# InkTime_v6.net
KiCad netlist of a schematic drawn in EAGLE
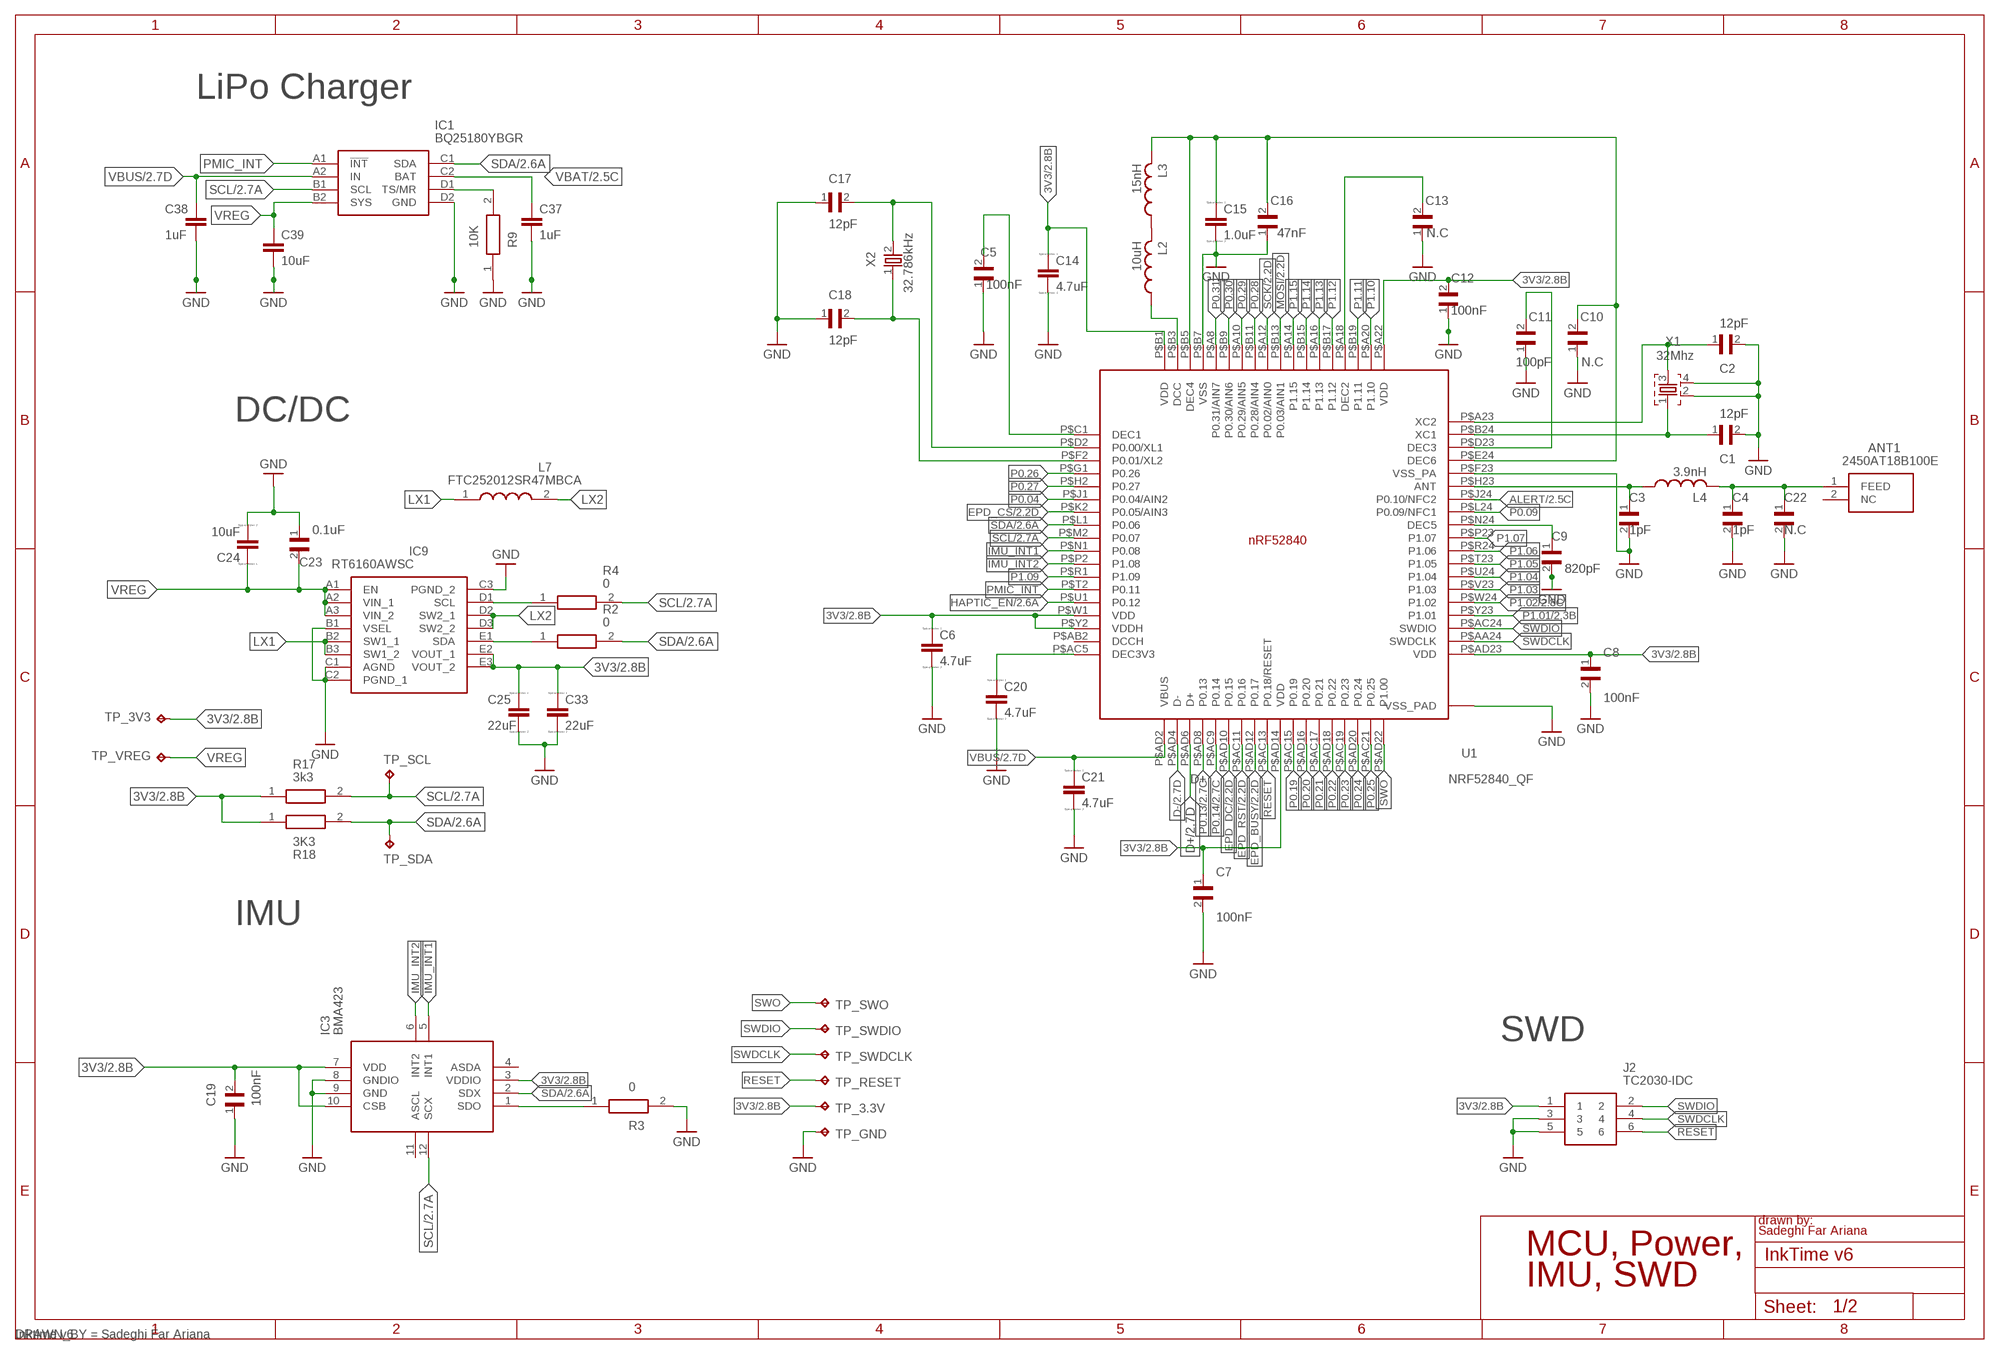
[diagram p0: schematic, sheet 1]
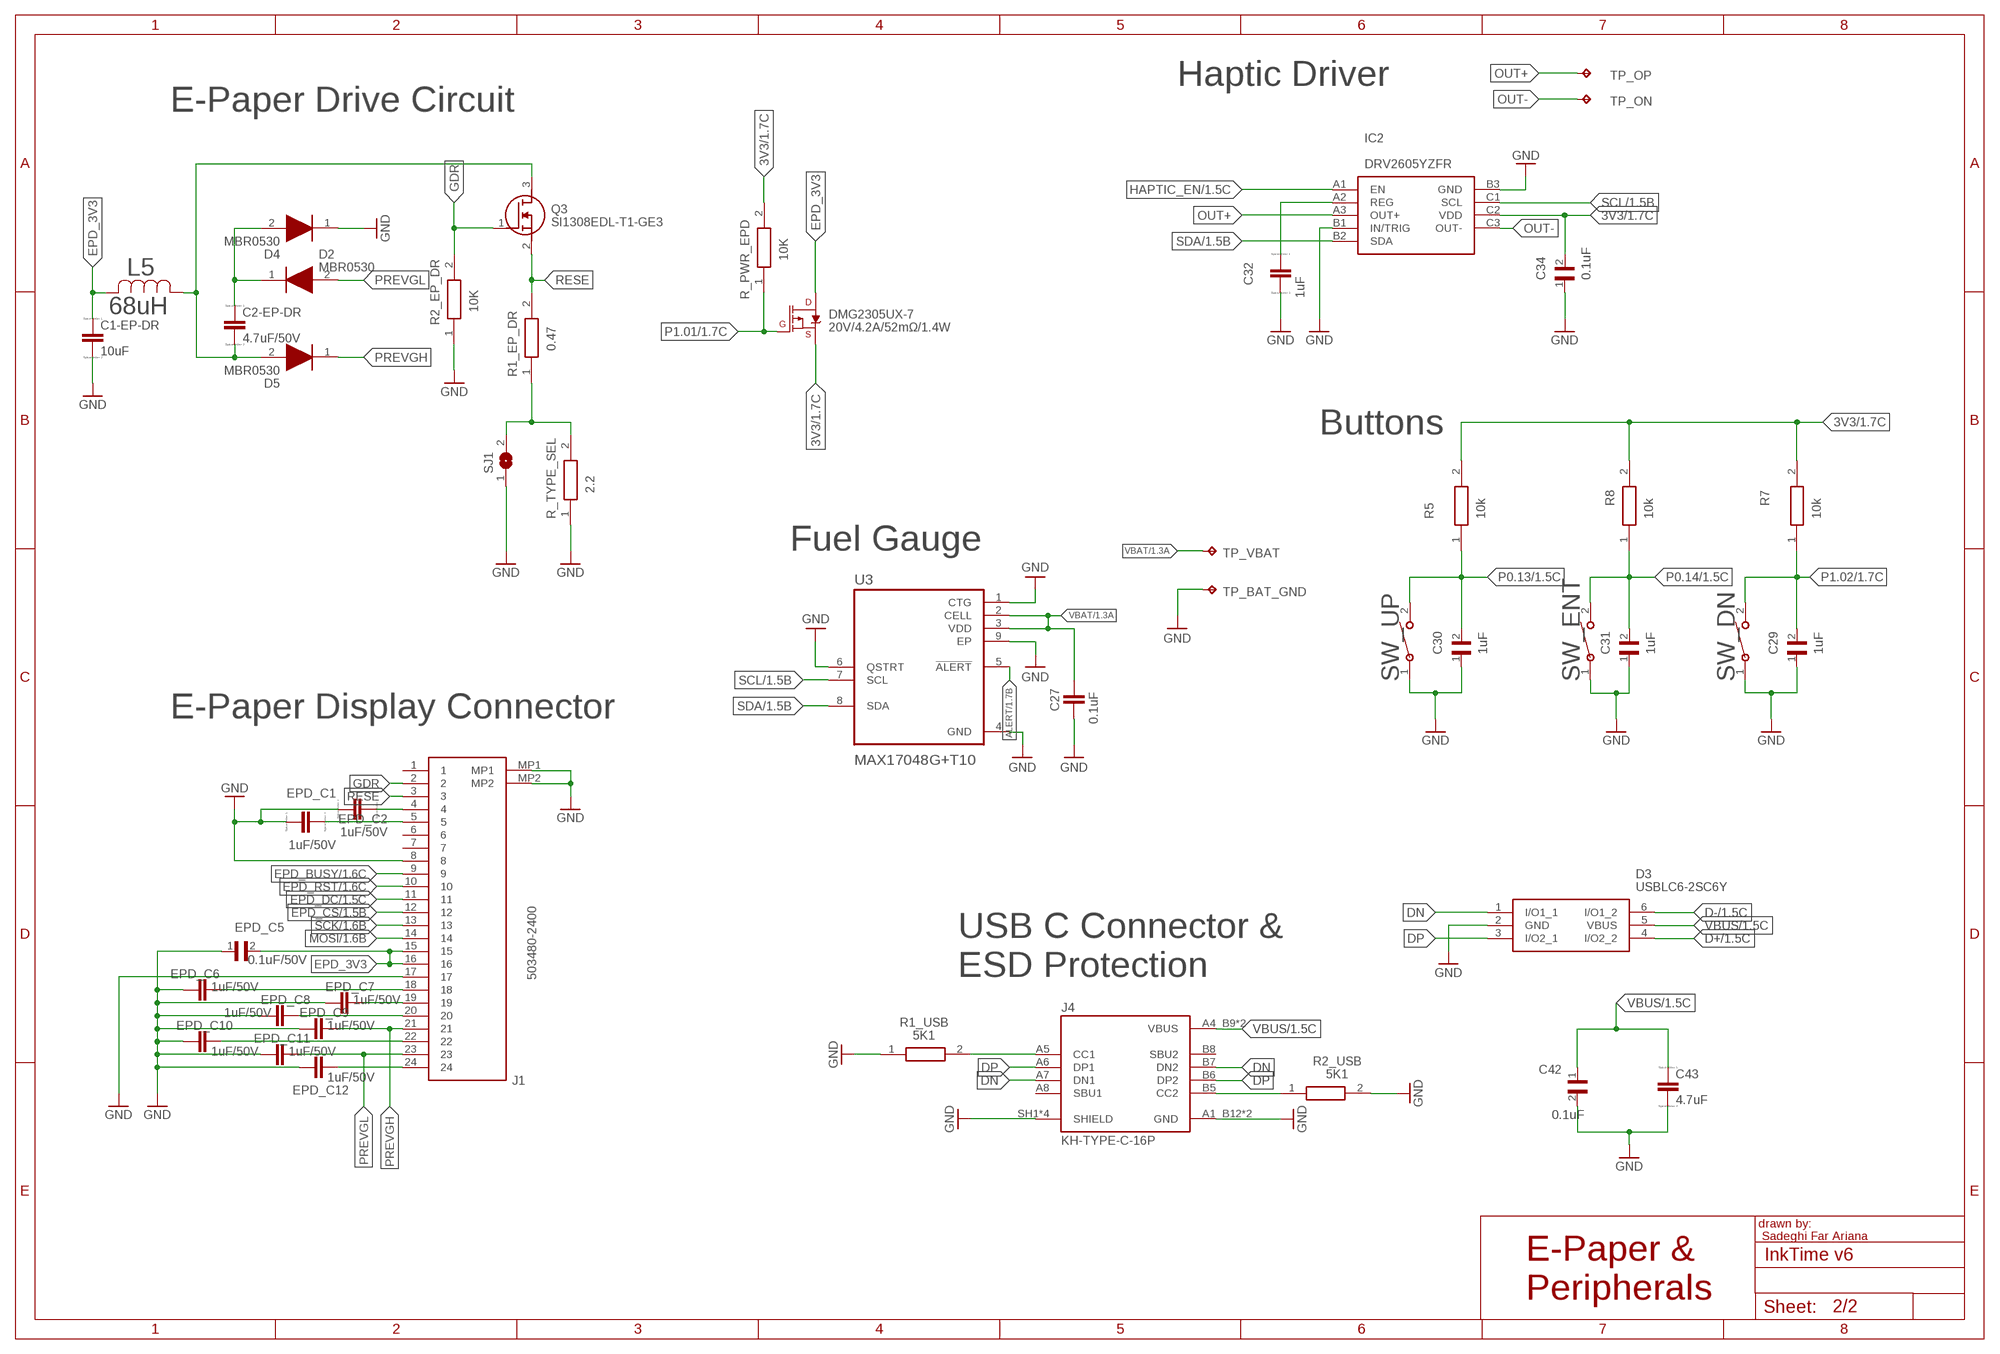
[diagram p1: schematic, sheet 2]

(export (version "E")
  (design (tool "Eeschema 10.0.6"))
  (components
    (comp (ref "C1-EP-DR")
      (value "10uF")
      (footprint "eagle-import:ESP32_C6_LIBRARY_1_ESP32_WROVER_EAGLE-LTSPICE_C0402")
      (libsource (lib "eagle-import") (part "ESP32_C6_LIBRARY_1_ESP32_WROVER_EAGLE-LTSPICE_CC0402"))
    )
    (comp (ref "C2-EP-DR")
      (value "4.7uF/50V")
      (footprint "eagle-import:ESP32_C6_LIBRARY_1_ESP32_WROVER_EAGLE-LTSPICE_C0402")
      (libsource (lib "eagle-import") (part "ESP32_C6_LIBRARY_1_ESP32_WROVER_EAGLE-LTSPICE_CC0402"))
    )
    (comp (ref "C27")
      (value "0.1uF")
      (footprint "eagle-import:NORDIC_NRF_3_RESC0201_L")
      (libsource (lib "eagle-import") (part "NORDIC_NRF_3_CAPACITOR_0201_L"))
    )
    (comp (ref "C29")
      (value "1uF")
      (footprint "eagle-import:GRM011R60J152KE01L_2_CAPC0201X13N")
      (fields (field (name "MF") "Murata") (field (name "MP") "GRM011R60J152KE01L"))
      (libsource (lib "eagle-import") (part "GRM011R60J152KE01L_2_GRM011R60J152KE01L"))
    )
    (comp (ref "C30")
      (value "1uF")
      (footprint "eagle-import:GRM011R60J152KE01L_2_CAPC0201X13N")
      (fields (field (name "MF") "Murata") (field (name "MP") "GRM011R60J152KE01L"))
      (libsource (lib "eagle-import") (part "GRM011R60J152KE01L_2_GRM011R60J152KE01L"))
    )
    (comp (ref "C31")
      (value "1uF")
      (footprint "eagle-import:GRM011R60J152KE01L_2_CAPC0201X13N")
      (fields (field (name "MF") "Murata") (field (name "MP") "GRM011R60J152KE01L"))
      (libsource (lib "eagle-import") (part "GRM011R60J152KE01L_2_GRM011R60J152KE01L"))
    )
    (comp (ref "C32")
      (value "1uF")
      (footprint "eagle-import:ESP32_C6_LIBRARY_1_ESP32_WROVER_EAGLE-LTSPICE_C0402")
      (libsource (lib "eagle-import") (part "ESP32_C6_LIBRARY_1_ESP32_WROVER_EAGLE-LTSPICE_CC0402"))
    )
    (comp (ref "C34")
      (value "0.1uF")
      (footprint "eagle-import:GRM011R60J152KE01L_2_CAPC0201X13N")
      (fields (field (name "MF") "Murata") (field (name "MP") "GRM011R60J152KE01L"))
      (libsource (lib "eagle-import") (part "GRM011R60J152KE01L_2_GRM011R60J152KE01L"))
    )
    (comp (ref "C42")
      (value "0.1uF")
      (footprint "eagle-import:GRM011R60J152KE01L_2_CAPC0201X13N")
      (fields (field (name "MF") "Murata") (field (name "MP") "GRM011R60J152KE01L"))
      (libsource (lib "eagle-import") (part "GRM011R60J152KE01L_2_GRM011R60J152KE01L"))
    )
    (comp (ref "C43")
      (value "4.7uF")
      (footprint "eagle-import:ESP32_C6_LIBRARY_1_ESP32_WROVER_EAGLE-LTSPICE_C0402")
      (libsource (lib "eagle-import") (part "ESP32_C6_LIBRARY_1_ESP32_WROVER_EAGLE-LTSPICE_CC0402"))
    )
    (comp (ref "D2")
      (value "MBR0530")
      (footprint "eagle-import:ESP32_C6_LIBRARY_5_SOD3716X135N")
      (fields (field (name "MF") "ON Semiconductor"))
      (libsource (lib "eagle-import") (part "ESP32_C6_LIBRARY_5_MBR0530"))
    )
    (comp (ref "D3")
      (value "USBLC6-2SC6Y")
      (footprint "eagle-import:ESP32_C6_LIBRARY_3_SOT95P280X145-6N")
      (fields (field (name "MF") "STMicroelectronics"))
      (libsource (lib "eagle-import") (part "ESP32_C6_LIBRARY_3_USBLC6-2SC6Y"))
    )
    (comp (ref "D4")
      (value "MBR0530")
      (footprint "eagle-import:ESP32_C6_LIBRARY_5_SOD3716X135N")
      (fields (field (name "MF") "ON Semiconductor"))
      (libsource (lib "eagle-import") (part "ESP32_C6_LIBRARY_5_MBR0530"))
    )
    (comp (ref "D5")
      (value "MBR0530")
      (footprint "eagle-import:ESP32_C6_LIBRARY_5_SOD3716X135N")
      (fields (field (name "MF") "ON Semiconductor"))
      (libsource (lib "eagle-import") (part "ESP32_C6_LIBRARY_5_MBR0530"))
    )
    (comp (ref "DMG2305UX-7")
      (value "20V/4.2A/52mΩ/1.4W")
      (footprint "eagle-import:ESP32_C6_LIBRARY_4_ESP32_C6_LIBRARY_4_ESP32_C6_LIBRARY_4_ESP32_C6_LIBRARY_4_ESP32_WROVER_SPARKFUN-DISCRETESEMI_SOT23-3")
      (libsource (lib "eagle-import") (part "ESP32_C6_LIBRARY_4_ESP32_WROVER_SPARKFUN-DISCRETESEMI_MOSFET_PCH-DMG2305UX-7"))
    )
    (comp (ref "EPD_C1")
      (value "1uF/50V")
      (footprint "eagle-import:ESP32_C6_LIBRARY_1_ESP32_WROVER_EAGLE-LTSPICE_C0402")
      (libsource (lib "eagle-import") (part "ESP32_C6_LIBRARY_1_ESP32_WROVER_EAGLE-LTSPICE_CC0402"))
    )
    (comp (ref "EPD_C2")
      (value "1uF/50V")
      (footprint "eagle-import:ESP32_C6_LIBRARY_1_ESP32_WROVER_EAGLE-LTSPICE_C0402")
      (libsource (lib "eagle-import") (part "ESP32_C6_LIBRARY_1_ESP32_WROVER_EAGLE-LTSPICE_CC0402"))
    )
    (comp (ref "EPD_C5")
      (value "0.1uF/50V")
      (footprint "eagle-import:GRM011R60J152KE01L_2_CAPC0201X13N")
      (fields (field (name "MF") "Murata") (field (name "MP") "GRM011R60J152KE01L"))
      (libsource (lib "eagle-import") (part "GRM011R60J152KE01L_2_GRM011R60J152KE01L"))
    )
    (comp (ref "EPD_C6")
      (value "1uF/50V")
      (footprint "eagle-import:NORDIC_NRF_3_RESC0402_L")
      (libsource (lib "eagle-import") (part "NORDIC_NRF_3_CAPACITOR_0402_L"))
    )
    (comp (ref "EPD_C7")
      (value "1uF/50V")
      (footprint "eagle-import:NORDIC_NRF_3_RESC0402_L")
      (libsource (lib "eagle-import") (part "NORDIC_NRF_3_CAPACITOR_0402_L"))
    )
    (comp (ref "EPD_C8")
      (value "1uF/50V")
      (footprint "eagle-import:NORDIC_NRF_3_RESC0402_L")
      (libsource (lib "eagle-import") (part "NORDIC_NRF_3_CAPACITOR_0402_L"))
    )
    (comp (ref "EPD_C9")
      (value "1uF/50V")
      (footprint "eagle-import:NORDIC_NRF_3_RESC0402_L")
      (libsource (lib "eagle-import") (part "NORDIC_NRF_3_CAPACITOR_0402_L"))
    )
    (comp (ref "EPD_C10")
      (value "1uF/50V")
      (footprint "eagle-import:NORDIC_NRF_3_RESC0402_L")
      (libsource (lib "eagle-import") (part "NORDIC_NRF_3_CAPACITOR_0402_L"))
    )
    (comp (ref "EPD_C11")
      (value "1uF/50V")
      (footprint "eagle-import:NORDIC_NRF_3_RESC0402_L")
      (libsource (lib "eagle-import") (part "NORDIC_NRF_3_CAPACITOR_0402_L"))
    )
    (comp (ref "EPD_C12")
      (value "1uF/50V")
      (footprint "eagle-import:NORDIC_NRF_3_RESC0402_L")
      (libsource (lib "eagle-import") (part "NORDIC_NRF_3_CAPACITOR_0402_L"))
    )
    (comp (ref "IC2")
      (value "DRV2605YZFR")
      (footprint "eagle-import:DRV2605YZFR_BGA9C50P3X3_144X144X62")
      (libsource (lib "eagle-import") (part "DRV2605YZFR_DRV2605YZFR"))
    )
    (comp (ref "J1")
      (value "503480-2400")
      (footprint "eagle-import:503480-2400_5034802400")
      (fields (field (name "MOUSER_PART_NUMBER") "538-503480-2400"))
      (libsource (lib "eagle-import") (part "503480-2400_503480-2400"))
    )
    (comp (ref "J4")
      (value "KH-TYPE-C-16P")
      (footprint "eagle-import:KH-TYPE-C-16P_KINGHELM_KH-TYPE-C-16P")
      (fields (field (name "MF") "kinghelm"))
      (libsource (lib "eagle-import") (part "KH-TYPE-C-16P_KH-TYPE-C-16P"))
    )
    (comp (ref "L5")
      (value "68uH")
      (footprint "eagle-import:ESP32_C6_LIBRARY_2_IND_4828-WE-TPC_WRE")
      (fields
        (field (name "MANUFACTURER_PART_NUMBER") "744043680")
        (field (name "COPYRIGHT") "Copyright (C) 2024 Ultra Librarian. All rights reserved.")
      )
      (libsource (lib "eagle-import") (part "ESP32_C6_LIBRARY_2_744043680IND_4828-WE-TPC_WRE"))
    )
    (comp (ref "Q3")
      (value "SI1308EDL-T1-GE3")
      (footprint "eagle-import:ESP32_C6_LIBRARY_6_SOT65P210X110-3N")
      (fields (field (name "MF") "Vishay Siliconix"))
      (libsource (lib "eagle-import") (part "ESP32_C6_LIBRARY_6_SI1308EDL-T1-GE3"))
    )
    (comp (ref "R1_EP_DR")
      (value "0.47")
      (footprint "eagle-import:CPF0201D7K68C1_0201")
      (libsource (lib "eagle-import") (part "CPF0201D7K68C1_CPF0201D7K68C1"))
    )
    (comp (ref "R1_USB")
      (value "5K1")
      (footprint "eagle-import:CPF0201D7K68C1_0201")
      (libsource (lib "eagle-import") (part "CPF0201D7K68C1_CPF0201D7K68C1"))
    )
    (comp (ref "R2_EP_DR")
      (value "10K")
      (footprint "eagle-import:CPF0201D7K68C1_0201")
      (libsource (lib "eagle-import") (part "CPF0201D7K68C1_CPF0201D7K68C1"))
    )
    (comp (ref "R2_USB")
      (value "5K1")
      (footprint "eagle-import:CPF0201D7K68C1_0201")
      (libsource (lib "eagle-import") (part "CPF0201D7K68C1_CPF0201D7K68C1"))
    )
    (comp (ref "R5")
      (value "10k")
      (footprint "eagle-import:CPF0201D7K68C1_0201")
      (libsource (lib "eagle-import") (part "CPF0201D7K68C1_CPF0201D7K68C1"))
    )
    (comp (ref "R7")
      (value "10k")
      (footprint "eagle-import:CPF0201D7K68C1_0201")
      (libsource (lib "eagle-import") (part "CPF0201D7K68C1_CPF0201D7K68C1"))
    )
    (comp (ref "R8")
      (value "10k")
      (footprint "eagle-import:CPF0201D7K68C1_0201")
      (libsource (lib "eagle-import") (part "CPF0201D7K68C1_CPF0201D7K68C1"))
    )
    (comp (ref "R_PWR_EPD")
      (value "10K")
      (footprint "eagle-import:CPF0201D7K68C1_0201")
      (libsource (lib "eagle-import") (part "CPF0201D7K68C1_CPF0201D7K68C1"))
    )
    (comp (ref "R_TYPE_SEL")
      (value "2.2")
      (footprint "eagle-import:CPF0201D7K68C1_0201")
      (libsource (lib "eagle-import") (part "CPF0201D7K68C1_CPF0201D7K68C1"))
    )
    (comp (ref "SJ1")
      (value "ESP32_C6_LIBRARY_7_JUMPER_SJ")
      (footprint "eagle-import:ESP32_C6_LIBRARY_7_JUMPER_SJ")
      (libsource (lib "eagle-import") (part "ESP32_C6_LIBRARY_7_JUMPER_SJ"))
    )
    (comp (ref "SW_DN")
      (value "2025-10-22_07-23-44_LIBRARY_EVP-AKE31ASW_EVP-AKE31A_PAN")
      (footprint "eagle-import:2025-10-22_07-23-44_LIBRARY_SW_EVP-AKE31A_PAN")
      (fields
        (field (name "MANUFACTURER_PART_NUMBER") "EVP-AKE31A")
        (field (name "COPYRIGHT") "Copyright (C) 2025 Ultra Librarian. All rights reserved.")
      )
      (libsource (lib "eagle-import") (part "2025-10-22_07-23-44_LIBRARY_EVP-AKE31ASW_EVP-AKE31A_PAN"))
    )
    (comp (ref "SW_ENT")
      (value "2025-10-22_07-23-44_LIBRARY_EVP-AKE31ASW_EVP-AKE31A_PAN")
      (footprint "eagle-import:2025-10-22_07-23-44_LIBRARY_SW_EVP-AKE31A_PAN")
      (fields
        (field (name "MANUFACTURER_PART_NUMBER") "EVP-AKE31A")
        (field (name "COPYRIGHT") "Copyright (C) 2025 Ultra Librarian. All rights reserved.")
      )
      (libsource (lib "eagle-import") (part "2025-10-22_07-23-44_LIBRARY_EVP-AKE31ASW_EVP-AKE31A_PAN"))
    )
    (comp (ref "SW_UP")
      (value "2025-10-22_07-23-44_LIBRARY_EVP-AKE31ASW_EVP-AKE31A_PAN")
      (footprint "eagle-import:2025-10-22_07-23-44_LIBRARY_SW_EVP-AKE31A_PAN")
      (fields
        (field (name "MANUFACTURER_PART_NUMBER") "EVP-AKE31A")
        (field (name "COPYRIGHT") "Copyright (C) 2025 Ultra Librarian. All rights reserved.")
      )
      (libsource (lib "eagle-import") (part "2025-10-22_07-23-44_LIBRARY_EVP-AKE31ASW_EVP-AKE31A_PAN"))
    )
    (comp (ref "TP_BAT_GND")
      (value "HECTOR_WATCH_1_TPTP20R")
      (footprint "eagle-import:HECTOR_WATCH_1_TP20R")
      (libsource (lib "eagle-import") (part "HECTOR_WATCH_1_TPTP20R"))
    )
    (comp (ref "TP_ON")
      (value "HECTOR_WATCH_1_TPTP20R")
      (footprint "eagle-import:HECTOR_WATCH_1_TP20R")
      (libsource (lib "eagle-import") (part "HECTOR_WATCH_1_TPTP20R"))
    )
    (comp (ref "TP_OP")
      (value "HECTOR_WATCH_1_TPTP20R")
      (footprint "eagle-import:HECTOR_WATCH_1_TP20R")
      (libsource (lib "eagle-import") (part "HECTOR_WATCH_1_TPTP20R"))
    )
    (comp (ref "TP_VBAT")
      (value "HECTOR_WATCH_1_TPTP20R")
      (footprint "eagle-import:HECTOR_WATCH_1_TP20R")
      (libsource (lib "eagle-import") (part "HECTOR_WATCH_1_TPTP20R"))
    )
    (comp (ref "U3")
      (value "MAX17048G+T10")
      (footprint "eagle-import:ESP32_C6_LIBRARY_SON50P200X200X80-9N")
      (fields (field (name "MF") "Analog Devices"))
      (libsource (lib "eagle-import") (part "ESP32_C6_LIBRARY_MAX17048G+T10"))
    )
    (comp (ref "ANT1")
      (value "2450AT18B100E")
      (footprint "eagle-import:2450AT18B100E_ANTC3216X140N")
      (fields (field (name "MOUSER_PART_NUMBER") "609-2450AT18B100E"))
      (libsource (lib "eagle-import") (part "2450AT18B100E_2450AT18B100E"))
    )
    (comp (ref "C1")
      (value "12pF")
      (footprint "eagle-import:GRM011R60J152KE01L_1_0201")
      (libsource (lib "eagle-import") (part "GRM011R60J152KE01L_1_GRM011R60J152KE01L"))
    )
    (comp (ref "C2")
      (value "12pF")
      (footprint "eagle-import:GRM011R60J152KE01L_1_0201")
      (libsource (lib "eagle-import") (part "GRM011R60J152KE01L_1_GRM011R60J152KE01L"))
    )
    (comp (ref "C3")
      (value "1pF")
      (footprint "eagle-import:GRM011R60J152KE01L_1_0201")
      (libsource (lib "eagle-import") (part "GRM011R60J152KE01L_1_GRM011R60J152KE01L"))
    )
    (comp (ref "C4")
      (value "1pF")
      (footprint "eagle-import:GRM011R60J152KE01L_1_0201")
      (libsource (lib "eagle-import") (part "GRM011R60J152KE01L_1_GRM011R60J152KE01L"))
    )
    (comp (ref "C5")
      (value "100nF")
      (footprint "eagle-import:GRM011R60J152KE01L_1_0201")
      (libsource (lib "eagle-import") (part "GRM011R60J152KE01L_1_GRM011R60J152KE01L"))
    )
    (comp (ref "C6")
      (value "4.7uF")
      (footprint "eagle-import:ESP32_C6_LIBRARY_1_ESP32_WROVER_EAGLE-LTSPICE_C0402")
      (libsource (lib "eagle-import") (part "ESP32_C6_LIBRARY_1_ESP32_WROVER_EAGLE-LTSPICE_CC0402"))
    )
    (comp (ref "C7")
      (value "100nF")
      (footprint "eagle-import:GRM011R60J152KE01L_1_0201")
      (libsource (lib "eagle-import") (part "GRM011R60J152KE01L_1_GRM011R60J152KE01L"))
    )
    (comp (ref "C8")
      (value "100nF")
      (footprint "eagle-import:GRM011R60J152KE01L_1_0201")
      (libsource (lib "eagle-import") (part "GRM011R60J152KE01L_1_GRM011R60J152KE01L"))
    )
    (comp (ref "C9")
      (value "820pF")
      (footprint "eagle-import:GRM011R60J152KE01L_1_0201")
      (libsource (lib "eagle-import") (part "GRM011R60J152KE01L_1_GRM011R60J152KE01L"))
    )
    (comp (ref "C10")
      (value "N.C")
      (footprint "eagle-import:GRM011R60J152KE01L_1_0201")
      (libsource (lib "eagle-import") (part "GRM011R60J152KE01L_1_GRM011R60J152KE01L"))
    )
    (comp (ref "C11")
      (value "100pF")
      (footprint "eagle-import:GRM011R60J152KE01L_1_0201")
      (libsource (lib "eagle-import") (part "GRM011R60J152KE01L_1_GRM011R60J152KE01L"))
    )
    (comp (ref "C12")
      (value "100nF")
      (footprint "eagle-import:GRM011R60J152KE01L_1_0201")
      (libsource (lib "eagle-import") (part "GRM011R60J152KE01L_1_GRM011R60J152KE01L"))
    )
    (comp (ref "C13")
      (value "N.C")
      (footprint "eagle-import:GRM011R60J152KE01L_1_0201")
      (libsource (lib "eagle-import") (part "GRM011R60J152KE01L_1_GRM011R60J152KE01L"))
    )
    (comp (ref "C14")
      (value "4.7uF")
      (footprint "eagle-import:ESP32_C6_LIBRARY_1_ESP32_WROVER_EAGLE-LTSPICE_C0402")
      (libsource (lib "eagle-import") (part "ESP32_C6_LIBRARY_1_ESP32_WROVER_EAGLE-LTSPICE_CC0402"))
    )
    (comp (ref "C15")
      (value "1.0uF")
      (footprint "eagle-import:ESP32_C6_LIBRARY_1_ESP32_WROVER_EAGLE-LTSPICE_C0402")
      (libsource (lib "eagle-import") (part "ESP32_C6_LIBRARY_1_ESP32_WROVER_EAGLE-LTSPICE_CC0402"))
    )
    (comp (ref "C16")
      (value "47nF")
      (footprint "eagle-import:GRM011R60J152KE01L_1_0201")
      (libsource (lib "eagle-import") (part "GRM011R60J152KE01L_1_GRM011R60J152KE01L"))
    )
    (comp (ref "C17")
      (value "12pF")
      (footprint "eagle-import:GRM011R60J152KE01L_1_0201")
      (libsource (lib "eagle-import") (part "GRM011R60J152KE01L_1_GRM011R60J152KE01L"))
    )
    (comp (ref "C18")
      (value "12pF")
      (footprint "eagle-import:GRM011R60J152KE01L_1_0201")
      (libsource (lib "eagle-import") (part "GRM011R60J152KE01L_1_GRM011R60J152KE01L"))
    )
    (comp (ref "C19")
      (value "100nF")
      (footprint "eagle-import:GRM011R60J152KE01L_1_0201")
      (libsource (lib "eagle-import") (part "GRM011R60J152KE01L_1_GRM011R60J152KE01L"))
    )
    (comp (ref "C20")
      (value "4.7uF")
      (footprint "eagle-import:ESP32_C6_LIBRARY_1_ESP32_WROVER_EAGLE-LTSPICE_C0402")
      (libsource (lib "eagle-import") (part "ESP32_C6_LIBRARY_1_ESP32_WROVER_EAGLE-LTSPICE_CC0402"))
    )
    (comp (ref "C21")
      (value "4.7uF")
      (footprint "eagle-import:ESP32_C6_LIBRARY_1_ESP32_WROVER_EAGLE-LTSPICE_C0402")
      (libsource (lib "eagle-import") (part "ESP32_C6_LIBRARY_1_ESP32_WROVER_EAGLE-LTSPICE_CC0402"))
    )
    (comp (ref "C22")
      (value "N.C")
      (footprint "eagle-import:GRM011R60J152KE01L_1_0201")
      (libsource (lib "eagle-import") (part "GRM011R60J152KE01L_1_GRM011R60J152KE01L"))
    )
    (comp (ref "C23")
      (value "0.1uF")
      (footprint "eagle-import:GRM011R60J152KE01L_1_0201")
      (libsource (lib "eagle-import") (part "GRM011R60J152KE01L_1_GRM011R60J152KE01L"))
    )
    (comp (ref "C24")
      (value "10uF")
      (footprint "eagle-import:ESP32_C6_LIBRARY_1_ESP32_WROVER_EAGLE-LTSPICE_C0402")
      (libsource (lib "eagle-import") (part "ESP32_C6_LIBRARY_1_ESP32_WROVER_EAGLE-LTSPICE_CC0402"))
    )
    (comp (ref "C25")
      (value "22uF")
      (footprint "eagle-import:ESP32_C6_LIBRARY_1_ESP32_WROVER_EAGLE-LTSPICE_C0402")
      (libsource (lib "eagle-import") (part "ESP32_C6_LIBRARY_1_ESP32_WROVER_EAGLE-LTSPICE_CC0402"))
    )
    (comp (ref "C33")
      (value "22uF")
      (footprint "eagle-import:ESP32_C6_LIBRARY_1_ESP32_WROVER_EAGLE-LTSPICE_C0402")
      (libsource (lib "eagle-import") (part "ESP32_C6_LIBRARY_1_ESP32_WROVER_EAGLE-LTSPICE_CC0402"))
    )
    (comp (ref "C37")
      (value "1uF")
      (footprint "eagle-import:PERFECT_0402_0402")
      (libsource (lib "eagle-import") (part "PERFECT_0402_CAP_0402"))
    )
    (comp (ref "C38")
      (value "1uF")
      (footprint "eagle-import:PERFECT_0402_0402")
      (libsource (lib "eagle-import") (part "PERFECT_0402_CAP_0402"))
    )
    (comp (ref "C39")
      (value "10uF")
      (footprint "eagle-import:PERFECT_0402_0402")
      (libsource (lib "eagle-import") (part "PERFECT_0402_CAP_0402"))
    )
    (comp (ref "IC1")
      (value "BQ25180YBGR")
      (footprint "eagle-import:BQ25180YBGR_BGA8C40P2X4_100X155X50")
      (fields (field (name "MOUSER_PART_NUMBER") "595-BQ25180YBGR"))
      (libsource (lib "eagle-import") (part "BQ25180YBGR_BQ25180YBGR"))
    )
    (comp (ref "IC3")
      (value "BMA423")
      (footprint "eagle-import:BMA423_BMA423")
      (fields (field (name "MOUSER_PART_NUMBER") "262-BMA423"))
      (libsource (lib "eagle-import") (part "BMA423_BMA423"))
    )
    (comp (ref "IC9")
      (value "RT6160AWSC")
      (footprint "eagle-import:RT6160AWSC_BGA15C40P3X5_140X230X60")
      (fields (field (name "MOUSER_PART_NUMBER") "835-RT6160AWSC"))
      (libsource (lib "eagle-import") (part "RT6160AWSC_RT6160AWSC"))
    )
    (comp (ref "J2")
      (value "TC2030-IDC")
      (footprint "eagle-import:TC2030-IDC_TC2030IDC")
      (libsource (lib "eagle-import") (part "TC2030-IDC_TC2030-IDC"))
    )
    (comp (ref "L2")
      (value "10uH")
      (footprint "eagle-import:NORDIC_NRF_2_RESC0402_L")
      (libsource (lib "eagle-import") (part "NORDIC_NRF_2_INDUCTOR_0402_L"))
    )
    (comp (ref "L3")
      (value "15nH")
      (footprint "eagle-import:NORDIC_NRF_2_RESC0402_L")
      (libsource (lib "eagle-import") (part "NORDIC_NRF_2_INDUCTOR_0402_L"))
    )
    (comp (ref "L4")
      (value "3.9nH")
      (footprint "eagle-import:NORDIC_NRF_2_RESC0402_L")
      (libsource (lib "eagle-import") (part "NORDIC_NRF_2_INDUCTOR_0402_L"))
    )
    (comp (ref "L7")
      (value "FTC252012SR47MBCA")
      (footprint "eagle-import:MLP2016SR47MT0S1_INDC2016X100N")
      (libsource (lib "eagle-import") (part "MLP2016SR47MT0S1_FTC252012SR47MBCA"))
    )
    (comp (ref "R2")
      (value "0")
      (footprint "eagle-import:CPF0201D7K68C1_0201")
      (libsource (lib "eagle-import") (part "CPF0201D7K68C1_CPF0201D7K68C1"))
    )
    (comp (ref "R3")
      (value "0")
      (footprint "eagle-import:CPF0201D7K68C1_0201")
      (libsource (lib "eagle-import") (part "CPF0201D7K68C1_CPF0201D7K68C1"))
    )
    (comp (ref "R4")
      (value "0")
      (footprint "eagle-import:CPF0201D7K68C1_0201")
      (libsource (lib "eagle-import") (part "CPF0201D7K68C1_CPF0201D7K68C1"))
    )
    (comp (ref "R9")
      (value "10K")
      (footprint "eagle-import:ERA-1AEB3401C_0201")
      (libsource (lib "eagle-import") (part "ERA-1AEB3401C_CPF0201D7K68C1"))
    )
    (comp (ref "R17")
      (value "3k3")
      (footprint "eagle-import:CPF0201D7K68C1_0201")
      (libsource (lib "eagle-import") (part "CPF0201D7K68C1_CPF0201D7K68C1"))
    )
    (comp (ref "R18")
      (value "3K3")
      (footprint "eagle-import:CPF0201D7K68C1_0201")
      (libsource (lib "eagle-import") (part "CPF0201D7K68C1_CPF0201D7K68C1"))
    )
    (comp (ref "TP_3.3V")
      (value "HECTOR_WATCH_1_TPTP20R")
      (footprint "eagle-import:HECTOR_WATCH_1_TP20R")
      (libsource (lib "eagle-import") (part "HECTOR_WATCH_1_TPTP20R"))
    )
    (comp (ref "TP_3V3")
      (value "HECTOR_WATCH_1_TPTP20R")
      (footprint "eagle-import:HECTOR_WATCH_1_TP20R")
      (libsource (lib "eagle-import") (part "HECTOR_WATCH_1_TPTP20R"))
    )
    (comp (ref "TP_GND")
      (value "HECTOR_WATCH_1_TPTP20R")
      (footprint "eagle-import:HECTOR_WATCH_1_TP20R")
      (libsource (lib "eagle-import") (part "HECTOR_WATCH_1_TPTP20R"))
    )
    (comp (ref "TP_RESET")
      (value "HECTOR_WATCH_1_TPTP20R")
      (footprint "eagle-import:HECTOR_WATCH_1_TP20R")
      (libsource (lib "eagle-import") (part "HECTOR_WATCH_1_TPTP20R"))
    )
    (comp (ref "TP_SCL")
      (value "HECTOR_WATCH_1_TPTP20R")
      (footprint "eagle-import:HECTOR_WATCH_1_TP20R")
      (libsource (lib "eagle-import") (part "HECTOR_WATCH_1_TPTP20R"))
    )
    (comp (ref "TP_SDA")
      (value "HECTOR_WATCH_1_TPTP20R")
      (footprint "eagle-import:HECTOR_WATCH_1_TP20R")
      (libsource (lib "eagle-import") (part "HECTOR_WATCH_1_TPTP20R"))
    )
    (comp (ref "TP_SWDCLK")
      (value "HECTOR_WATCH_1_TPTP20R")
      (footprint "eagle-import:HECTOR_WATCH_1_TP20R")
      (libsource (lib "eagle-import") (part "HECTOR_WATCH_1_TPTP20R"))
    )
    (comp (ref "TP_SWDIO")
      (value "HECTOR_WATCH_1_TPTP20R")
      (footprint "eagle-import:HECTOR_WATCH_1_TP20R")
      (libsource (lib "eagle-import") (part "HECTOR_WATCH_1_TPTP20R"))
    )
    (comp (ref "TP_SWO")
      (value "HECTOR_WATCH_1_TPTP20R")
      (footprint "eagle-import:HECTOR_WATCH_1_TP20R")
      (libsource (lib "eagle-import") (part "HECTOR_WATCH_1_TPTP20R"))
    )
    (comp (ref "TP_VREG")
      (value "HECTOR_WATCH_1_TPTP20R")
      (footprint "eagle-import:HECTOR_WATCH_1_TP20R")
      (libsource (lib "eagle-import") (part "HECTOR_WATCH_1_TPTP20R"))
    )
    (comp (ref "U1")
      (value "NRF52840_QF")
      (footprint "eagle-import:NORDIC_NRF_4_AQFN50P700X700X85_HS-74N")
      (libsource (lib "eagle-import") (part "NORDIC_NRF_4_NRF52840_QF"))
    )
    (comp (ref "X1")
      (value "32Mhz")
      (footprint "eagle-import:NORDIC_NRF_BT-XTAL_2016_N")
      (libsource (lib "eagle-import") (part "NORDIC_NRF_XTAL_32MHZ"))
    )
    (comp (ref "X2")
      (value "32.786kHz")
      (footprint "eagle-import:NORDIC_NRF_1_XTAL_3215_N")
      (libsource (lib "eagle-import") (part "NORDIC_NRF_1_XTAL_32KHZ"))
    )
  )
  (nets
    (net (code "1") (name "3V3") (class "Default")
      (node (ref "C12") (pin "2") (pinfunction "2_2") (pintype "passive"))
      (node (ref "C14") (pin "1") (pinfunction "1_1") (pintype "passive"))
      (node (ref "C19") (pin "2") (pinfunction "2_2") (pintype "passive"))
      (node (ref "C25") (pin "1") (pinfunction "1_1") (pintype "passive"))
      (node (ref "C33") (pin "1") (pinfunction "1_1") (pintype "passive"))
      (node (ref "C34") (pin "2") (pinfunction "2_2") (pintype "passive"))
      (node (ref "C6") (pin "1") (pinfunction "1_1") (pintype "passive"))
      (node (ref "C7") (pin "1") (pinfunction "1_1") (pintype "passive"))
      (node (ref "C8") (pin "1") (pinfunction "1_1") (pintype "passive"))
      (node (ref "DMG2305UX-7") (pin "2") (pinfunction "S_2") (pintype "bidirectional"))
      (node (ref "IC2") (pin "C2") (pinfunction "VDD_C2") (pintype "bidirectional"))
      (node (ref "IC3") (pin "10") (pinfunction "CSB_10") (pintype "bidirectional"))
      (node (ref "IC3") (pin "3") (pinfunction "VDDIO_3") (pintype "bidirectional"))
      (node (ref "IC3") (pin "7") (pinfunction "VDD_7") (pintype "bidirectional"))
      (node (ref "IC9") (pin "E2") (pinfunction "VOUT_1_E2") (pintype "bidirectional"))
      (node (ref "IC9") (pin "E3") (pinfunction "VOUT_2_E3") (pintype "bidirectional"))
      (node (ref "J2") (pin "1") (pinfunction "1_1") (pintype "bidirectional"))
      (node (ref "R17") (pin "1") (pinfunction "1_1") (pintype "bidirectional"))
      (node (ref "R18") (pin "1") (pinfunction "1_1") (pintype "bidirectional"))
      (node (ref "R5") (pin "2") (pinfunction "2_2") (pintype "bidirectional"))
      (node (ref "R7") (pin "2") (pinfunction "2_2") (pintype "bidirectional"))
      (node (ref "R8") (pin "2") (pinfunction "2_2") (pintype "bidirectional"))
      (node (ref "R_PWR_EPD") (pin "2") (pinfunction "2_2") (pintype "bidirectional"))
      (node (ref "TP_3.3V") (pin "TP") (pinfunction "TP_TP") (pintype "input"))
      (node (ref "TP_3V3") (pin "TP") (pinfunction "TP_TP") (pintype "input"))
      (node (ref "U1") (pin "P$A22") (pinfunction "VDD_P$A22") (pintype "power_in"))
      (node (ref "U1") (pin "P$AD14") (pinfunction "VDD_P$AD14") (pintype "power_in"))
      (node (ref "U1") (pin "P$AD23") (pinfunction "VDD_P$AD23") (pintype "power_in"))
      (node (ref "U1") (pin "P$B1") (pinfunction "VDD_P$B1") (pintype "power_in"))
      (node (ref "U1") (pin "P$W1") (pinfunction "VDD_P$W1") (pintype "power_in"))
      (node (ref "U1") (pin "P$Y2") (pinfunction "VDDH_P$Y2") (pintype "power_in"))
    )
    (net (code "2") (name "ALERT") (class "Default")
      (node (ref "U1") (pin "P$J24") (pinfunction "P0.10/NFC2_P$J24") (pintype "bidirectional"))
      (node (ref "U3") (pin "5") (pinfunction "~{ALERT}_5") (pintype "output"))
    )
    (net (code "3") (name "D+") (class "Default")
      (node (ref "D3") (pin "4") (pinfunction "I/O2_2_4") (pintype "bidirectional"))
      (node (ref "U1") (pin "P$AD6") (pinfunction "D+_P$AD6") (pintype "bidirectional"))
    )
    (net (code "4") (name "D-") (class "Default")
      (node (ref "D3") (pin "6") (pinfunction "I/O1_2_6") (pintype "bidirectional"))
      (node (ref "U1") (pin "P$AD4") (pinfunction "D-_P$AD4") (pintype "bidirectional"))
    )
    (net (code "5") (name "DN") (class "Default")
      (node (ref "D3") (pin "1") (pinfunction "I/O1_1_1") (pintype "bidirectional"))
      (node (ref "J4") (pin "A7") (pinfunction "DN1_A7") (pintype "bidirectional"))
      (node (ref "J4") (pin "B7") (pinfunction "DN2_B7") (pintype "bidirectional"))
    )
    (net (code "6") (name "DP") (class "Default")
      (node (ref "D3") (pin "3") (pinfunction "I/O2_1_3") (pintype "bidirectional"))
      (node (ref "J4") (pin "A6") (pinfunction "DP1_A6") (pintype "bidirectional"))
      (node (ref "J4") (pin "B6") (pinfunction "DP2_B6") (pintype "bidirectional"))
    )
    (net (code "7") (name "EPD_3V3") (class "Default")
      (node (ref "C1-EP-DR") (pin "1") (pinfunction "1_1") (pintype "passive"))
      (node (ref "DMG2305UX-7") (pin "3") (pinfunction "D_3") (pintype "bidirectional"))
      (node (ref "EPD_C5") (pin "2") (pinfunction "2_2") (pintype "passive"))
      (node (ref "J1") (pin "15") (pinfunction "15_15") (pintype "bidirectional"))
      (node (ref "J1") (pin "16") (pinfunction "16_16") (pintype "bidirectional"))
      (node (ref "L5") (pin "2") (pinfunction "2_2") (pintype "passive"))
    )
    (net (code "8") (name "EPD_BUSY") (class "Default")
      (node (ref "J1") (pin "9") (pinfunction "9_9") (pintype "bidirectional"))
      (node (ref "U1") (pin "P$AD12") (pinfunction "P0.17_P$AD12") (pintype "bidirectional"))
    )
    (net (code "9") (name "EPD_CS") (class "Default")
      (node (ref "J1") (pin "12") (pinfunction "12_12") (pintype "bidirectional"))
      (node (ref "U1") (pin "P$K2") (pinfunction "P0.05/AIN3_P$K2") (pintype "bidirectional"))
    )
    (net (code "10") (name "EPD_DC") (class "Default")
      (node (ref "J1") (pin "11") (pinfunction "11_11") (pintype "bidirectional"))
      (node (ref "U1") (pin "P$AD10") (pinfunction "P0.15_P$AD10") (pintype "bidirectional"))
    )
    (net (code "11") (name "EPD_RST") (class "Default")
      (node (ref "J1") (pin "10") (pinfunction "10_10") (pintype "bidirectional"))
      (node (ref "U1") (pin "P$AC11") (pinfunction "P0.16_P$AC11") (pintype "bidirectional"))
    )
    (net (code "12") (name "GDR") (class "Default")
      (node (ref "J1") (pin "2") (pinfunction "2_2") (pintype "bidirectional"))
      (node (ref "Q3") (pin "1") (pinfunction "G_1") (pintype "bidirectional"))
      (node (ref "R2_EP_DR") (pin "2") (pinfunction "2_2") (pintype "bidirectional"))
    )
    (net (code "13") (name "GND") (class "Default")
      (node (ref "C1") (pin "2") (pinfunction "2_2") (pintype "passive"))
      (node (ref "C1-EP-DR") (pin "2") (pinfunction "2_2") (pintype "passive"))
      (node (ref "C10") (pin "1") (pinfunction "1_1") (pintype "passive"))
      (node (ref "C11") (pin "1") (pinfunction "1_1") (pintype "passive"))
      (node (ref "C12") (pin "1") (pinfunction "1_1") (pintype "passive"))
      (node (ref "C13") (pin "1") (pinfunction "1_1") (pintype "passive"))
      (node (ref "C14") (pin "2") (pinfunction "2_2") (pintype "passive"))
      (node (ref "C15") (pin "2") (pinfunction "2_2") (pintype "passive"))
      (node (ref "C16") (pin "1") (pinfunction "1_1") (pintype "passive"))
      (node (ref "C17") (pin "1") (pinfunction "1_1") (pintype "passive"))
      (node (ref "C18") (pin "1") (pinfunction "1_1") (pintype "passive"))
      (node (ref "C19") (pin "1") (pinfunction "1_1") (pintype "passive"))
      (node (ref "C2") (pin "2") (pinfunction "2_2") (pintype "passive"))
      (node (ref "C20") (pin "2") (pinfunction "2_2") (pintype "passive"))
      (node (ref "C21") (pin "2") (pinfunction "2_2") (pintype "passive"))
      (node (ref "C22") (pin "2") (pinfunction "2_2") (pintype "passive"))
      (node (ref "C23") (pin "1") (pinfunction "1_1") (pintype "passive"))
      (node (ref "C24") (pin "2") (pinfunction "2_2") (pintype "passive"))
      (node (ref "C25") (pin "2") (pinfunction "2_2") (pintype "passive"))
      (node (ref "C27") (pin "2") (pinfunction "2_2") (pintype "passive"))
      (node (ref "C29") (pin "1") (pinfunction "1_1") (pintype "passive"))
      (node (ref "C3") (pin "2") (pinfunction "2_2") (pintype "passive"))
      (node (ref "C30") (pin "1") (pinfunction "1_1") (pintype "passive"))
      (node (ref "C31") (pin "1") (pinfunction "1_1") (pintype "passive"))
      (node (ref "C32") (pin "2") (pinfunction "2_2") (pintype "passive"))
      (node (ref "C33") (pin "2") (pinfunction "2_2") (pintype "passive"))
      (node (ref "C34") (pin "1") (pinfunction "1_1") (pintype "passive"))
      (node (ref "C37") (pin "2") (pinfunction "2_2") (pintype "passive"))
      (node (ref "C38") (pin "2") (pinfunction "2_2") (pintype "passive"))
      (node (ref "C39") (pin "2") (pinfunction "2_2") (pintype "passive"))
      (node (ref "C4") (pin "2") (pinfunction "2_2") (pintype "passive"))
      (node (ref "C42") (pin "2") (pinfunction "2_2") (pintype "passive"))
      (node (ref "C43") (pin "2") (pinfunction "2_2") (pintype "passive"))
      (node (ref "C5") (pin "1") (pinfunction "1_1") (pintype "passive"))
      (node (ref "C6") (pin "2") (pinfunction "2_2") (pintype "passive"))
      (node (ref "C7") (pin "2") (pinfunction "2_2") (pintype "passive"))
      (node (ref "C8") (pin "2") (pinfunction "2_2") (pintype "passive"))
      (node (ref "C9") (pin "2") (pinfunction "2_2") (pintype "passive"))
      (node (ref "D3") (pin "2") (pinfunction "GND_2") (pintype "bidirectional"))
      (node (ref "D4") (pin "1") (pinfunction "K_1") (pintype "bidirectional"))
      (node (ref "EPD_C1") (pin "1") (pinfunction "1_1") (pintype "passive"))
      (node (ref "EPD_C10") (pin "1") (pinfunction "1_1") (pintype "passive"))
      (node (ref "EPD_C11") (pin "1") (pinfunction "1_1") (pintype "passive"))
      (node (ref "EPD_C12") (pin "1") (pinfunction "1_1") (pintype "passive"))
      (node (ref "EPD_C2") (pin "1") (pinfunction "1_1") (pintype "passive"))
      (node (ref "EPD_C5") (pin "1") (pinfunction "1_1") (pintype "passive"))
      (node (ref "EPD_C6") (pin "1") (pinfunction "1_1") (pintype "passive"))
      (node (ref "EPD_C7") (pin "1") (pinfunction "1_1") (pintype "passive"))
      (node (ref "EPD_C8") (pin "1") (pinfunction "1_1") (pintype "passive"))
      (node (ref "EPD_C9") (pin "1") (pinfunction "1_1") (pintype "passive"))
      (node (ref "IC1") (pin "D2") (pinfunction "GND_D2") (pintype "bidirectional"))
      (node (ref "IC2") (pin "B1") (pinfunction "IN/TRIG_B1") (pintype "bidirectional"))
      (node (ref "IC2") (pin "B3") (pinfunction "GND_B3") (pintype "bidirectional"))
      (node (ref "IC3") (pin "8") (pinfunction "GNDIO_8") (pintype "bidirectional"))
      (node (ref "IC3") (pin "9") (pinfunction "GND_9") (pintype "bidirectional"))
      (node (ref "IC9") (pin "B1") (pinfunction "VSEL_B1") (pintype "bidirectional"))
      (node (ref "IC9") (pin "C1") (pinfunction "AGND_C1") (pintype "bidirectional"))
      (node (ref "IC9") (pin "C2") (pinfunction "PGND_1_C2") (pintype "bidirectional"))
      (node (ref "IC9") (pin "C3") (pinfunction "PGND_2_C3") (pintype "bidirectional"))
      (node (ref "J1") (pin "17") (pinfunction "17_17") (pintype "bidirectional"))
      (node (ref "J1") (pin "8") (pinfunction "8_8") (pintype "bidirectional"))
      (node (ref "J1") (pin "MP1") (pinfunction "MP1_MP1") (pintype "bidirectional"))
      (node (ref "J1") (pin "MP2") (pinfunction "MP2_MP2") (pintype "bidirectional"))
      (node (ref "J2") (pin "3") (pinfunction "3_3") (pintype "bidirectional"))
      (node (ref "J2") (pin "5") (pinfunction "5_5") (pintype "bidirectional"))
      (node (ref "J4") (pin "A12_B1") (pinfunction "GND_A12_B1") (pintype "power_in"))
      (node (ref "J4") (pin "A1_B12") (pinfunction "GND_A1_B12") (pintype "power_in"))
      (node (ref "J4") (pin "SH1") (pinfunction "SHIELD_SH1") (pintype "passive"))
      (node (ref "J4") (pin "SH2") (pinfunction "SHIELD_SH2") (pintype "passive"))
      (node (ref "J4") (pin "SH3") (pinfunction "SHIELD_SH3") (pintype "passive"))
      (node (ref "J4") (pin "SH4") (pinfunction "SHIELD_SH4") (pintype "passive"))
      (node (ref "R1_USB") (pin "1") (pinfunction "1_1") (pintype "bidirectional"))
      (node (ref "R2_EP_DR") (pin "1") (pinfunction "1_1") (pintype "bidirectional"))
      (node (ref "R2_USB") (pin "2") (pinfunction "2_2") (pintype "bidirectional"))
      (node (ref "R3") (pin "2") (pinfunction "2_2") (pintype "bidirectional"))
      (node (ref "R9") (pin "1") (pinfunction "1_1") (pintype "bidirectional"))
      (node (ref "R_TYPE_SEL") (pin "1") (pinfunction "1_1") (pintype "bidirectional"))
      (node (ref "SJ1") (pin "1") (pinfunction "1_1") (pintype "passive"))
      (node (ref "SW_DN") (pin "1") (pinfunction "1_1") (pintype "passive"))
      (node (ref "SW_ENT") (pin "1") (pinfunction "1_1") (pintype "passive"))
      (node (ref "SW_UP") (pin "1") (pinfunction "1_1") (pintype "passive"))
      (node (ref "TP_BAT_GND") (pin "TP") (pinfunction "TP_TP") (pintype "input"))
      (node (ref "TP_GND") (pin "TP") (pinfunction "TP_TP") (pintype "input"))
      (node (ref "U1") (pin "P$74") (pinfunction "VSS_PAD_P$74") (pintype "bidirectional"))
      (node (ref "U1") (pin "P$75") (pinfunction "VSS_PAD_P$75") (pintype "bidirectional"))
      (node (ref "U1") (pin "P$76") (pinfunction "VSS_PAD_P$76") (pintype "bidirectional"))
      (node (ref "U1") (pin "P$77") (pinfunction "VSS_PAD_P$77") (pintype "bidirectional"))
      (node (ref "U1") (pin "P$78") (pinfunction "VSS_PAD_P$78") (pintype "bidirectional"))
      (node (ref "U1") (pin "P$79") (pinfunction "VSS_PAD_P$79") (pintype "bidirectional"))
      (node (ref "U1") (pin "P$80") (pinfunction "VSS_PAD_P$80") (pintype "bidirectional"))
      (node (ref "U1") (pin "P$81") (pinfunction "VSS_PAD_P$81") (pintype "bidirectional"))
      (node (ref "U1") (pin "P$82") (pinfunction "VSS_PAD_P$82") (pintype "bidirectional"))
      (node (ref "U1") (pin "P$83") (pinfunction "VSS_PAD_P$83") (pintype "bidirectional"))
      (node (ref "U1") (pin "P$84") (pinfunction "VSS_PAD_P$84") (pintype "bidirectional"))
      (node (ref "U1") (pin "P$85") (pinfunction "VSS_PAD_P$85") (pintype "bidirectional"))
      (node (ref "U1") (pin "P$86") (pinfunction "VSS_PAD_P$86") (pintype "bidirectional"))
      (node (ref "U1") (pin "P$87") (pinfunction "VSS_PAD_P$87") (pintype "bidirectional"))
      (node (ref "U1") (pin "P$88") (pinfunction "VSS_PAD_P$88") (pintype "bidirectional"))
      (node (ref "U1") (pin "P$89") (pinfunction "VSS_PAD_P$89") (pintype "bidirectional"))
      (node (ref "U1") (pin "P$90") (pinfunction "VSS_PAD_P$90") (pintype "bidirectional"))
      (node (ref "U1") (pin "P$B7") (pinfunction "VSS_P$B7") (pintype "power_in"))
      (node (ref "U1") (pin "P$F23") (pinfunction "VSS_PA_P$F23") (pintype "bidirectional"))
      (node (ref "U3") (pin "1") (pinfunction "CTG_1") (pintype "power_in"))
      (node (ref "U3") (pin "4") (pinfunction "GND_4") (pintype "power_in"))
      (node (ref "U3") (pin "6") (pinfunction "QSTRT_6") (pintype "input"))
      (node (ref "U3") (pin "9") (pinfunction "EP_9") (pintype "power_in"))
      (node (ref "X1") (pin "2") (pinfunction "2_2") (pintype "passive"))
      (node (ref "X1") (pin "4") (pinfunction "4_4") (pintype "passive"))
    )
    (net (code "14") (name "HAPTIC_EN") (class "Default")
      (node (ref "IC2") (pin "A1") (pinfunction "EN_A1") (pintype "bidirectional"))
      (node (ref "U1") (pin "P$U1") (pinfunction "P0.12_P$U1") (pintype "bidirectional"))
    )
    (net (code "15") (name "IMU_INT1") (class "Default")
      (node (ref "IC3") (pin "5") (pinfunction "INT1_5") (pintype "bidirectional"))
      (node (ref "U1") (pin "P$N1") (pinfunction "P0.08_P$N1") (pintype "bidirectional"))
    )
    (net (code "16") (name "IMU_INT2") (class "Default")
      (node (ref "IC3") (pin "6") (pinfunction "INT2_6") (pintype "bidirectional"))
      (node (ref "U1") (pin "P$P2") (pinfunction "P1.08_P$P2") (pintype "bidirectional"))
    )
    (net (code "17") (name "LX1") (class "Default")
      (node (ref "IC9") (pin "B2") (pinfunction "SW1_1_B2") (pintype "bidirectional"))
      (node (ref "IC9") (pin "B3") (pinfunction "SW1_2_B3") (pintype "bidirectional"))
      (node (ref "L7") (pin "1") (pinfunction "1_1") (pintype "bidirectional"))
    )
    (net (code "18") (name "LX2") (class "Default")
      (node (ref "IC9") (pin "D2") (pinfunction "SW2_1_D2") (pintype "bidirectional"))
      (node (ref "IC9") (pin "D3") (pinfunction "SW2_2_D3") (pintype "bidirectional"))
      (node (ref "L7") (pin "2") (pinfunction "2_2") (pintype "bidirectional"))
    )
    (net (code "19") (name "MOSI") (class "Default")
      (node (ref "J1") (pin "14") (pinfunction "14_14") (pintype "bidirectional"))
      (node (ref "U1") (pin "P$B13") (pinfunction "P0.03/AIN1_P$B13") (pintype "bidirectional"))
    )
    (net (code "20") (name "Net-(ANT1-FEED)") (class "Default")
      (node (ref "ANT1") (pin "1") (pinfunction "FEED_1") (pintype "input"))
      (node (ref "C22") (pin "1") (pinfunction "1_1") (pintype "passive"))
      (node (ref "C4") (pin "1") (pinfunction "1_1") (pintype "passive"))
      (node (ref "L4") (pin "2") (pinfunction "2_2") (pintype "passive"))
    )
    (net (code "21") (name "Net-(D2-K)") (class "Default")
      (node (ref "C2-EP-DR") (pin "1") (pinfunction "1_1") (pintype "passive"))
      (node (ref "D2") (pin "1") (pinfunction "K_1") (pintype "bidirectional"))
      (node (ref "D4") (pin "2") (pinfunction "A_2") (pintype "bidirectional"))
    )
    (net (code "22") (name "Net-(D5-A)") (class "Default")
      (node (ref "C2-EP-DR") (pin "2") (pinfunction "2_2") (pintype "passive"))
      (node (ref "D5") (pin "2") (pinfunction "A_2") (pintype "bidirectional"))
      (node (ref "L5") (pin "1") (pinfunction "1_1") (pintype "passive"))
      (node (ref "Q3") (pin "3") (pinfunction "D_3") (pintype "bidirectional"))
    )
    (net (code "23") (name "Net-(EPD_C1-Pad2)") (class "Default")
      (node (ref "EPD_C1") (pin "2") (pinfunction "2_2") (pintype "passive"))
      (node (ref "J1") (pin "5") (pinfunction "5_5") (pintype "bidirectional"))
    )
    (net (code "24") (name "Net-(EPD_C2-Pad2)") (class "Default")
      (node (ref "EPD_C2") (pin "2") (pinfunction "2_2") (pintype "passive"))
      (node (ref "J1") (pin "4") (pinfunction "4_4") (pintype "bidirectional"))
    )
    (net (code "25") (name "Net-(EPD_C6-Pad2)") (class "Default")
      (node (ref "EPD_C6") (pin "2") (pinfunction "2_2") (pintype "passive"))
      (node (ref "J1") (pin "18") (pinfunction "18_18") (pintype "bidirectional"))
    )
    (net (code "26") (name "Net-(EPD_C7-Pad2)") (class "Default")
      (node (ref "EPD_C7") (pin "2") (pinfunction "2_2") (pintype "passive"))
      (node (ref "J1") (pin "19") (pinfunction "19_19") (pintype "bidirectional"))
    )
    (net (code "27") (name "Net-(EPD_C8-Pad2)") (class "Default")
      (node (ref "EPD_C8") (pin "2") (pinfunction "2_2") (pintype "passive"))
      (node (ref "J1") (pin "20") (pinfunction "20_20") (pintype "bidirectional"))
    )
    (net (code "28") (name "Net-(EPD_C10-Pad2)") (class "Default")
      (node (ref "EPD_C10") (pin "2") (pinfunction "2_2") (pintype "passive"))
      (node (ref "J1") (pin "22") (pinfunction "22_22") (pintype "bidirectional"))
    )
    (net (code "29") (name "Net-(EPD_C12-Pad2)") (class "Default")
      (node (ref "EPD_C12") (pin "2") (pinfunction "2_2") (pintype "passive"))
      (node (ref "J1") (pin "24") (pinfunction "24_24") (pintype "bidirectional"))
    )
    (net (code "30") (name "Net-(IC1-TS{slash}MR)") (class "Default")
      (node (ref "IC1") (pin "D1") (pinfunction "TS/MR_D1") (pintype "bidirectional"))
      (node (ref "R9") (pin "2") (pinfunction "2_2") (pintype "bidirectional"))
    )
    (net (code "31") (name "Net-(IC2-REG)") (class "Default")
      (node (ref "C32") (pin "1") (pinfunction "1_1") (pintype "passive"))
      (node (ref "IC2") (pin "A2") (pinfunction "REG_A2") (pintype "bidirectional"))
    )
    (net (code "32") (name "Net-(IC3-SDO)") (class "Default")
      (node (ref "IC3") (pin "1") (pinfunction "SDO_1") (pintype "bidirectional"))
      (node (ref "R3") (pin "1") (pinfunction "1_1") (pintype "bidirectional"))
    )
    (net (code "33") (name "Net-(IC9-SCL)") (class "Default")
      (node (ref "IC9") (pin "D1") (pinfunction "SCL_D1") (pintype "bidirectional"))
      (node (ref "R4") (pin "1") (pinfunction "1_1") (pintype "bidirectional"))
    )
    (net (code "34") (name "Net-(IC9-SDA)") (class "Default")
      (node (ref "IC9") (pin "E1") (pinfunction "SDA_E1") (pintype "bidirectional"))
      (node (ref "R2") (pin "1") (pinfunction "1_1") (pintype "bidirectional"))
    )
    (net (code "35") (name "Net-(J4-CC1)") (class "Default")
      (node (ref "J4") (pin "A5") (pinfunction "CC1_A5") (pintype "bidirectional"))
      (node (ref "R1_USB") (pin "2") (pinfunction "2_2") (pintype "bidirectional"))
    )
    (net (code "36") (name "Net-(J4-CC2)") (class "Default")
      (node (ref "J4") (pin "B5") (pinfunction "CC2_B5") (pintype "bidirectional"))
      (node (ref "R2_USB") (pin "1") (pinfunction "1_1") (pintype "bidirectional"))
    )
    (net (code "37") (name "Net-(L2-Pad2)") (class "Default")
      (node (ref "L2") (pin "2") (pinfunction "2_2") (pintype "passive"))
      (node (ref "L3") (pin "1") (pinfunction "1_1") (pintype "passive"))
    )
    (net (code "38") (name "Net-(R1_EP_DR-Pad1)") (class "Default")
      (node (ref "R1_EP_DR") (pin "1") (pinfunction "1_1") (pintype "bidirectional"))
      (node (ref "R_TYPE_SEL") (pin "2") (pinfunction "2_2") (pintype "bidirectional"))
      (node (ref "SJ1") (pin "2") (pinfunction "2_2") (pintype "passive"))
    )
    (net (code "39") (name "Net-(U1-ANT)") (class "Default")
      (node (ref "C3") (pin "1") (pinfunction "1_1") (pintype "passive"))
      (node (ref "L4") (pin "1") (pinfunction "1_1") (pintype "passive"))
      (node (ref "U1") (pin "P$H23") (pinfunction "ANT_P$H23") (pintype "bidirectional"))
    )
    (net (code "40") (name "Net-(U1-DCC)") (class "Default")
      (node (ref "L2") (pin "1") (pinfunction "1_1") (pintype "passive"))
      (node (ref "U1") (pin "P$B3") (pinfunction "DCC_P$B3") (pintype "output"))
    )
    (net (code "41") (name "Net-(U1-DEC1)") (class "Default")
      (node (ref "C5") (pin "2") (pinfunction "2_2") (pintype "passive"))
      (node (ref "U1") (pin "P$C1") (pinfunction "DEC1_P$C1") (pintype "power_in"))
    )
    (net (code "42") (name "Net-(U1-DEC2)") (class "Default")
      (node (ref "C13") (pin "2") (pinfunction "2_2") (pintype "passive"))
      (node (ref "U1") (pin "P$A18") (pinfunction "DEC2_P$A18") (pintype "bidirectional"))
    )
    (net (code "43") (name "Net-(U1-DEC3)") (class "Default")
      (node (ref "C11") (pin "2") (pinfunction "2_2") (pintype "passive"))
      (node (ref "U1") (pin "P$D23") (pinfunction "DEC3_P$D23") (pintype "bidirectional"))
    )
    (net (code "44") (name "Net-(U1-DEC3V3)") (class "Default")
      (node (ref "C20") (pin "1") (pinfunction "1_1") (pintype "passive"))
      (node (ref "U1") (pin "P$AC5") (pinfunction "DEC3V3_P$AC5") (pintype "bidirectional"))
    )
    (net (code "45") (name "Net-(U1-DEC4)") (class "Default")
      (node (ref "C10") (pin "2") (pinfunction "2_2") (pintype "passive"))
      (node (ref "C15") (pin "1") (pinfunction "1_1") (pintype "passive"))
      (node (ref "C16") (pin "2") (pinfunction "2_2") (pintype "passive"))
      (node (ref "L3") (pin "2") (pinfunction "2_2") (pintype "passive"))
      (node (ref "U1") (pin "P$B5") (pinfunction "DEC4_P$B5") (pintype "power_in"))
      (node (ref "U1") (pin "P$E24") (pinfunction "DEC6_P$E24") (pintype "bidirectional"))
    )
    (net (code "46") (name "Net-(U1-DEC5)") (class "Default")
      (node (ref "C9") (pin "1") (pinfunction "1_1") (pintype "passive"))
      (node (ref "U1") (pin "P$N24") (pinfunction "DEC5_P$N24") (pintype "bidirectional"))
    )
    (net (code "47") (name "Net-(U1-P0.00{slash}XL1)") (class "Default")
      (node (ref "C17") (pin "2") (pinfunction "2_2") (pintype "passive"))
      (node (ref "U1") (pin "P$D2") (pinfunction "P0.00/XL1_P$D2") (pintype "bidirectional"))
      (node (ref "X2") (pin "2") (pinfunction "2_2") (pintype "passive"))
    )
    (net (code "48") (name "Net-(U1-P0.01{slash}XL2)") (class "Default")
      (node (ref "C18") (pin "2") (pinfunction "2_2") (pintype "passive"))
      (node (ref "U1") (pin "P$F2") (pinfunction "P0.01/XL2_P$F2") (pintype "bidirectional"))
      (node (ref "X2") (pin "1") (pinfunction "1_1") (pintype "passive"))
    )
    (net (code "49") (name "Net-(U1-XC1)") (class "Default")
      (node (ref "C1") (pin "1") (pinfunction "1_1") (pintype "passive"))
      (node (ref "U1") (pin "P$B24") (pinfunction "XC1_P$B24") (pintype "input"))
      (node (ref "X1") (pin "1") (pinfunction "1_1") (pintype "passive"))
    )
    (net (code "50") (name "Net-(U1-XC2)") (class "Default")
      (node (ref "C2") (pin "1") (pinfunction "1_1") (pintype "passive"))
      (node (ref "U1") (pin "P$A23") (pinfunction "XC2_P$A23") (pintype "output"))
      (node (ref "X1") (pin "3") (pinfunction "3_3") (pintype "passive"))
    )
    (net (code "51") (name "OUT+") (class "Default")
      (node (ref "IC2") (pin "A3") (pinfunction "OUT+_A3") (pintype "bidirectional"))
      (node (ref "TP_OP") (pin "TP") (pinfunction "TP_TP") (pintype "input"))
    )
    (net (code "52") (name "OUT-") (class "Default")
      (node (ref "IC2") (pin "C3") (pinfunction "OUT-_C3") (pintype "bidirectional"))
      (node (ref "TP_ON") (pin "TP") (pinfunction "TP_TP") (pintype "input"))
    )
    (net (code "53") (name "P0.04") (class "Default")
      (node (ref "U1") (pin "P$J1") (pinfunction "P0.04/AIN2_P$J1") (pintype "bidirectional"))
    )
    (net (code "54") (name "P0.09") (class "Default")
      (node (ref "U1") (pin "P$L24") (pinfunction "P0.09/NFC1_P$L24") (pintype "bidirectional"))
    )
    (net (code "55") (name "P0.13") (class "Default")
      (node (ref "C30") (pin "2") (pinfunction "2_2") (pintype "passive"))
      (node (ref "R5") (pin "1") (pinfunction "1_1") (pintype "bidirectional"))
      (node (ref "SW_UP") (pin "2") (pinfunction "2_2") (pintype "passive"))
      (node (ref "U1") (pin "P$AD8") (pinfunction "P0.13_P$AD8") (pintype "bidirectional"))
    )
    (net (code "56") (name "P0.14") (class "Default")
      (node (ref "C31") (pin "2") (pinfunction "2_2") (pintype "passive"))
      (node (ref "R8") (pin "1") (pinfunction "1_1") (pintype "bidirectional"))
      (node (ref "SW_ENT") (pin "2") (pinfunction "2_2") (pintype "passive"))
      (node (ref "U1") (pin "P$AC9") (pinfunction "P0.14_P$AC9") (pintype "bidirectional"))
    )
    (net (code "57") (name "P0.19") (class "Default")
      (node (ref "U1") (pin "P$AC15") (pinfunction "P0.19_P$AC15") (pintype "bidirectional"))
    )
    (net (code "58") (name "P0.20") (class "Default")
      (node (ref "U1") (pin "P$AD16") (pinfunction "P0.20_P$AD16") (pintype "bidirectional"))
    )
    (net (code "59") (name "P0.21") (class "Default")
      (node (ref "U1") (pin "P$AC17") (pinfunction "P0.21_P$AC17") (pintype "bidirectional"))
    )
    (net (code "60") (name "P0.22") (class "Default")
      (node (ref "U1") (pin "P$AD18") (pinfunction "P0.22_P$AD18") (pintype "bidirectional"))
    )
    (net (code "61") (name "P0.23") (class "Default")
      (node (ref "U1") (pin "P$AC19") (pinfunction "P0.23_P$AC19") (pintype "bidirectional"))
    )
    (net (code "62") (name "P0.24") (class "Default")
      (node (ref "U1") (pin "P$AD20") (pinfunction "P0.24_P$AD20") (pintype "bidirectional"))
    )
    (net (code "63") (name "P0.25") (class "Default")
      (node (ref "U1") (pin "P$AC21") (pinfunction "P0.25_P$AC21") (pintype "bidirectional"))
    )
    (net (code "64") (name "P0.26") (class "Default")
      (node (ref "U1") (pin "P$G1") (pinfunction "P0.26_P$G1") (pintype "bidirectional"))
    )
    (net (code "65") (name "P0.27") (class "Default")
      (node (ref "U1") (pin "P$H2") (pinfunction "P0.27_P$H2") (pintype "bidirectional"))
    )
    (net (code "66") (name "P0.28") (class "Default")
      (node (ref "U1") (pin "P$B11") (pinfunction "P0.28/AIN4_P$B11") (pintype "bidirectional"))
    )
    (net (code "67") (name "P0.29") (class "Default")
      (node (ref "U1") (pin "P$A10") (pinfunction "P0.29/AIN5_P$A10") (pintype "bidirectional"))
    )
    (net (code "68") (name "P0.30") (class "Default")
      (node (ref "U1") (pin "P$B9") (pinfunction "P0.30/AIN6_P$B9") (pintype "bidirectional"))
    )
    (net (code "69") (name "P0.31") (class "Default")
      (node (ref "U1") (pin "P$A8") (pinfunction "P0.31/AIN7_P$A8") (pintype "bidirectional"))
    )
    (net (code "70") (name "P1.01") (class "Default")
      (node (ref "DMG2305UX-7") (pin "1") (pinfunction "G_1") (pintype "bidirectional"))
      (node (ref "R_PWR_EPD") (pin "1") (pinfunction "1_1") (pintype "bidirectional"))
      (node (ref "U1") (pin "P$Y23") (pinfunction "P1.01_P$Y23") (pintype "bidirectional"))
    )
    (net (code "71") (name "P1.02") (class "Default")
      (node (ref "C29") (pin "2") (pinfunction "2_2") (pintype "passive"))
      (node (ref "R7") (pin "1") (pinfunction "1_1") (pintype "bidirectional"))
      (node (ref "SW_DN") (pin "2") (pinfunction "2_2") (pintype "passive"))
      (node (ref "U1") (pin "P$W24") (pinfunction "P1.02_P$W24") (pintype "bidirectional"))
    )
    (net (code "72") (name "P1.03") (class "Default")
      (node (ref "U1") (pin "P$V23") (pinfunction "P1.03_P$V23") (pintype "bidirectional"))
    )
    (net (code "73") (name "P1.04") (class "Default")
      (node (ref "U1") (pin "P$U24") (pinfunction "P1.04_P$U24") (pintype "bidirectional"))
    )
    (net (code "74") (name "P1.05") (class "Default")
      (node (ref "U1") (pin "P$T23") (pinfunction "P1.05_P$T23") (pintype "bidirectional"))
    )
    (net (code "75") (name "P1.06") (class "Default")
      (node (ref "U1") (pin "P$R24") (pinfunction "P1.06_P$R24") (pintype "bidirectional"))
    )
    (net (code "76") (name "P1.07") (class "Default")
      (node (ref "U1") (pin "P$P23") (pinfunction "P1.07_P$P23") (pintype "bidirectional"))
    )
    (net (code "77") (name "P1.09") (class "Default")
      (node (ref "U1") (pin "P$R1") (pinfunction "P1.09_P$R1") (pintype "bidirectional"))
    )
    (net (code "78") (name "P1.10") (class "Default")
      (node (ref "U1") (pin "P$A20") (pinfunction "P1.10_P$A20") (pintype "bidirectional"))
    )
    (net (code "79") (name "P1.11") (class "Default")
      (node (ref "U1") (pin "P$B19") (pinfunction "P1.11_P$B19") (pintype "bidirectional"))
    )
    (net (code "80") (name "P1.12") (class "Default")
      (node (ref "U1") (pin "P$B17") (pinfunction "P1.12_P$B17") (pintype "bidirectional"))
    )
    (net (code "81") (name "P1.13") (class "Default")
      (node (ref "U1") (pin "P$A16") (pinfunction "P1.13_P$A16") (pintype "bidirectional"))
    )
    (net (code "82") (name "P1.14") (class "Default")
      (node (ref "U1") (pin "P$B15") (pinfunction "P1.14_P$B15") (pintype "bidirectional"))
    )
    (net (code "83") (name "P1.15") (class "Default")
      (node (ref "U1") (pin "P$A14") (pinfunction "P1.15_P$A14") (pintype "bidirectional"))
    )
    (net (code "84") (name "PMIC_INT") (class "Default")
      (node (ref "IC1") (pin "A1") (pinfunction "~{INT}_A1") (pintype "bidirectional"))
      (node (ref "U1") (pin "P$T2") (pinfunction "P0.11_P$T2") (pintype "bidirectional"))
    )
    (net (code "85") (name "PREVGH") (class "Default")
      (node (ref "D5") (pin "1") (pinfunction "K_1") (pintype "bidirectional"))
      (node (ref "EPD_C9") (pin "2") (pinfunction "2_2") (pintype "passive"))
      (node (ref "J1") (pin "21") (pinfunction "21_21") (pintype "bidirectional"))
    )
    (net (code "86") (name "PREVGL") (class "Default")
      (node (ref "D2") (pin "2") (pinfunction "A_2") (pintype "bidirectional"))
      (node (ref "EPD_C11") (pin "2") (pinfunction "2_2") (pintype "passive"))
      (node (ref "J1") (pin "23") (pinfunction "23_23") (pintype "bidirectional"))
    )
    (net (code "87") (name "RESE") (class "Default")
      (node (ref "J1") (pin "3") (pinfunction "3_3") (pintype "bidirectional"))
      (node (ref "Q3") (pin "2") (pinfunction "S_2") (pintype "bidirectional"))
      (node (ref "R1_EP_DR") (pin "2") (pinfunction "2_2") (pintype "bidirectional"))
    )
    (net (code "88") (name "RESET") (class "Default")
      (node (ref "J2") (pin "6") (pinfunction "6_6") (pintype "bidirectional"))
      (node (ref "TP_RESET") (pin "TP") (pinfunction "TP_TP") (pintype "input"))
      (node (ref "U1") (pin "P$AC13") (pinfunction "P0.18/RESET_P$AC13") (pintype "bidirectional"))
    )
    (net (code "89") (name "SCK") (class "Default")
      (node (ref "J1") (pin "13") (pinfunction "13_13") (pintype "bidirectional"))
      (node (ref "U1") (pin "P$A12") (pinfunction "P0.02/AIN0_P$A12") (pintype "bidirectional"))
    )
    (net (code "90") (name "SCL") (class "Default")
      (node (ref "IC1") (pin "B1") (pinfunction "SCL_B1") (pintype "bidirectional"))
      (node (ref "IC2") (pin "C1") (pinfunction "SCL_C1") (pintype "bidirectional"))
      (node (ref "IC3") (pin "12") (pinfunction "SCX_12") (pintype "bidirectional"))
      (node (ref "R17") (pin "2") (pinfunction "2_2") (pintype "bidirectional"))
      (node (ref "R4") (pin "2") (pinfunction "2_2") (pintype "bidirectional"))
      (node (ref "TP_SCL") (pin "TP") (pinfunction "TP_TP") (pintype "input"))
      (node (ref "U1") (pin "P$M2") (pinfunction "P0.07_P$M2") (pintype "bidirectional"))
      (node (ref "U3") (pin "7") (pinfunction "SCL_7") (pintype "input"))
    )
    (net (code "91") (name "SDA") (class "Default")
      (node (ref "IC1") (pin "C1") (pinfunction "SDA_C1") (pintype "bidirectional"))
      (node (ref "IC2") (pin "B2") (pinfunction "SDA_B2") (pintype "bidirectional"))
      (node (ref "IC3") (pin "2") (pinfunction "SDX_2") (pintype "bidirectional"))
      (node (ref "R18") (pin "2") (pinfunction "2_2") (pintype "bidirectional"))
      (node (ref "R2") (pin "2") (pinfunction "2_2") (pintype "bidirectional"))
      (node (ref "TP_SDA") (pin "TP") (pinfunction "TP_TP") (pintype "input"))
      (node (ref "U1") (pin "P$L1") (pinfunction "P0.06_P$L1") (pintype "bidirectional"))
      (node (ref "U3") (pin "8") (pinfunction "SDA_8") (pintype "bidirectional"))
    )
    (net (code "92") (name "SWDCLK") (class "Default")
      (node (ref "J2") (pin "4") (pinfunction "4_4") (pintype "bidirectional"))
      (node (ref "TP_SWDCLK") (pin "TP") (pinfunction "TP_TP") (pintype "input"))
      (node (ref "U1") (pin "P$AA24") (pinfunction "SWDCLK_P$AA24") (pintype "input"))
    )
    (net (code "93") (name "SWDIO") (class "Default")
      (node (ref "J2") (pin "2") (pinfunction "2_2") (pintype "bidirectional"))
      (node (ref "TP_SWDIO") (pin "TP") (pinfunction "TP_TP") (pintype "input"))
      (node (ref "U1") (pin "P$AC24") (pinfunction "SWDIO_P$AC24") (pintype "bidirectional"))
    )
    (net (code "94") (name "SWO") (class "Default")
      (node (ref "TP_SWO") (pin "TP") (pinfunction "TP_TP") (pintype "input"))
      (node (ref "U1") (pin "P$AD22") (pinfunction "P1.00_P$AD22") (pintype "bidirectional"))
    )
    (net (code "95") (name "VBAT") (class "Default")
      (node (ref "C27") (pin "1") (pinfunction "1_1") (pintype "passive"))
      (node (ref "C37") (pin "1") (pinfunction "1_1") (pintype "passive"))
      (node (ref "IC1") (pin "C2") (pinfunction "BAT_C2") (pintype "bidirectional"))
      (node (ref "TP_VBAT") (pin "TP") (pinfunction "TP_TP") (pintype "input"))
      (node (ref "U3") (pin "2") (pinfunction "CELL_2") (pintype "power_in"))
      (node (ref "U3") (pin "3") (pinfunction "VDD_3") (pintype "power_in"))
    )
    (net (code "96") (name "VBUS") (class "Default")
      (node (ref "C21") (pin "1") (pinfunction "1_1") (pintype "passive"))
      (node (ref "C38") (pin "1") (pinfunction "1_1") (pintype "passive"))
      (node (ref "C42") (pin "1") (pinfunction "1_1") (pintype "passive"))
      (node (ref "C43") (pin "1") (pinfunction "1_1") (pintype "passive"))
      (node (ref "D3") (pin "5") (pinfunction "VBUS_5") (pintype "bidirectional"))
      (node (ref "IC1") (pin "A2") (pinfunction "IN_A2") (pintype "bidirectional"))
      (node (ref "J4") (pin "A4_B9") (pinfunction "VBUS_A4_B9") (pintype "power_in"))
      (node (ref "J4") (pin "A9_B4") (pinfunction "VBUS_A9_B4") (pintype "power_in"))
      (node (ref "U1") (pin "P$AD2") (pinfunction "VBUS_P$AD2") (pintype "power_in"))
    )
    (net (code "97") (name "VREG") (class "Default")
      (node (ref "C23") (pin "2") (pinfunction "2_2") (pintype "passive"))
      (node (ref "C24") (pin "1") (pinfunction "1_1") (pintype "passive"))
      (node (ref "C39") (pin "1") (pinfunction "1_1") (pintype "passive"))
      (node (ref "IC1") (pin "B2") (pinfunction "SYS_B2") (pintype "bidirectional"))
      (node (ref "IC9") (pin "A1") (pinfunction "EN_A1") (pintype "bidirectional"))
      (node (ref "IC9") (pin "A2") (pinfunction "VIN_1_A2") (pintype "bidirectional"))
      (node (ref "IC9") (pin "A3") (pinfunction "VIN_2_A3") (pintype "bidirectional"))
      (node (ref "TP_VREG") (pin "TP") (pinfunction "TP_TP") (pintype "input"))
    )
    (net (code "98") (name "unconnected-(ANT1-NC-Pad2)") (class "Default")
      (node (ref "ANT1") (pin "2") (pinfunction "NC_2") (pintype "no_connect"))
    )
    (net (code "99") (name "unconnected-(IC3-ASCL-Pad11)") (class "Default")
      (node (ref "IC3") (pin "11") (pinfunction "ASCL_11") (pintype "bidirectional"))
    )
    (net (code "100") (name "unconnected-(IC3-ASDA-Pad4)") (class "Default")
      (node (ref "IC3") (pin "4") (pinfunction "ASDA_4") (pintype "bidirectional"))
    )
    (net (code "101") (name "unconnected-(J1-Pad1)") (class "Default")
      (node (ref "J1") (pin "1") (pinfunction "1_1") (pintype "bidirectional"))
    )
    (net (code "102") (name "unconnected-(J1-Pad6)") (class "Default")
      (node (ref "J1") (pin "6") (pinfunction "6_6") (pintype "bidirectional"))
    )
    (net (code "103") (name "unconnected-(J1-Pad7)") (class "Default")
      (node (ref "J1") (pin "7") (pinfunction "7_7") (pintype "bidirectional"))
    )
    (net (code "104") (name "unconnected-(J4-SBU1-PadA8)") (class "Default")
      (node (ref "J4") (pin "A8") (pinfunction "SBU1_A8") (pintype "bidirectional"))
    )
    (net (code "105") (name "unconnected-(J4-SBU2-PadB8)") (class "Default")
      (node (ref "J4") (pin "B8") (pinfunction "SBU2_B8") (pintype "bidirectional"))
    )
    (net (code "106") (name "unconnected-(U1-DCCH-PadP$AB2)") (class "Default")
      (node (ref "U1") (pin "P$AB2") (pinfunction "DCCH_P$AB2") (pintype "bidirectional"))
    )
  )
)
